# Display.net
KiCad netlist of a schematic drawn in Altium Designer
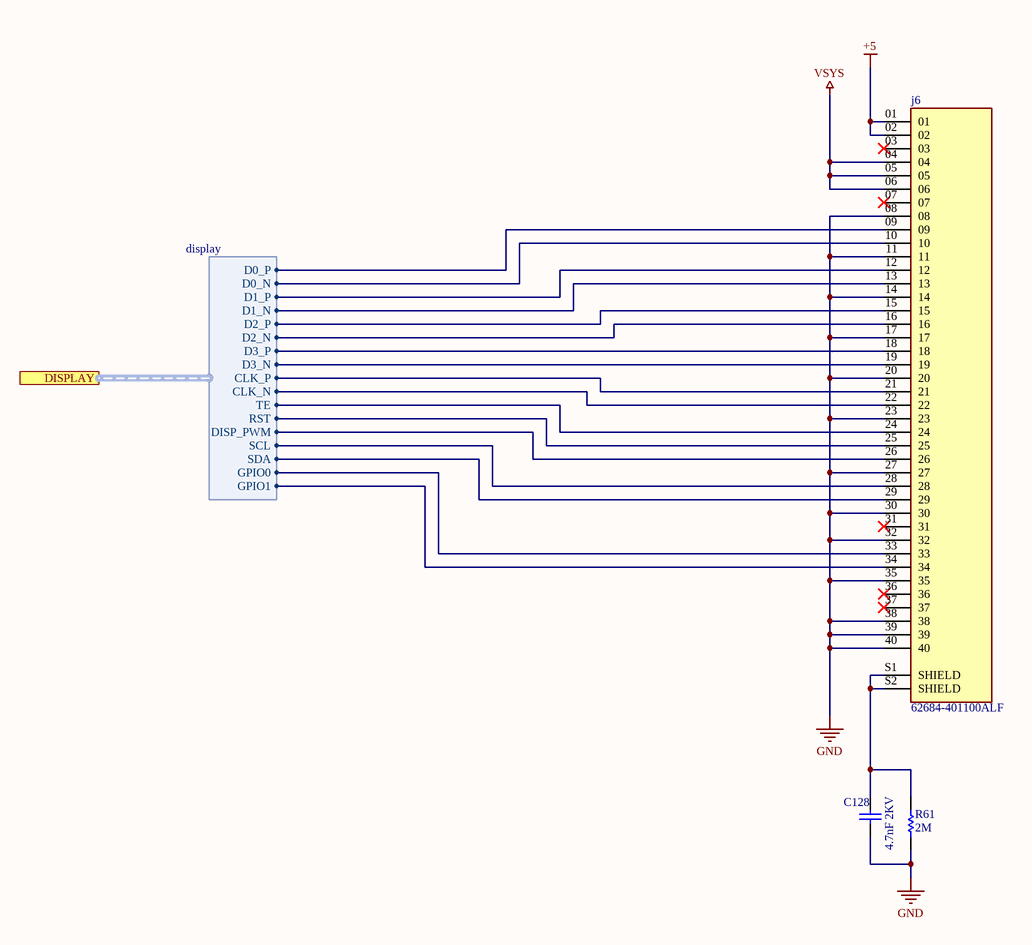
[diagram p0: Display.SchDoc]

(export (version "E")
  (design (tool "Eeschema 10.0.6"))
  (components
    (comp (ref "C128")
      (value "4.7nF 2KV")
      (footprint "C1210")
      (fields (field (name "Comment") "C1210"))
      (libsource (lib "kit") (part "C1210"))
    )
    (comp (ref "j6")
      (value "62684-401100ALF")
      (footprint "AMPHENOL_62684-401100ALF")
      (libsource (lib "kit") (part "62684-401100ALF"))
    )
    (comp (ref "R61")
      (value "2M")
      (footprint "R0603")
      (fields (field (name "Comment") "R0603"))
      (libsource (lib "kit") (part "R0603"))
    )
  )
  (nets
    (net (code "2") (name "+5") (class "Default")
      (node (ref "j6") (pin "01") (pinfunction "01_01") (pintype "passive"))
      (node (ref "j6") (pin "02") (pinfunction "02_02") (pintype "passive"))
    )
    (net (code "3") (name "/CLK_N") (class "Default")
      (node (ref "j6") (pin "22") (pinfunction "22_22") (pintype "passive"))
    )
    (net (code "4") (name "/CLK_P") (class "Default")
      (node (ref "j6") (pin "21") (pinfunction "21_21") (pintype "passive"))
    )
    (net (code "5") (name "/D0_N") (class "Default")
      (node (ref "j6") (pin "10") (pinfunction "10_10") (pintype "passive"))
    )
    (net (code "6") (name "/D0_P") (class "Default")
      (node (ref "j6") (pin "09") (pinfunction "09_09") (pintype "passive"))
    )
    (net (code "7") (name "/D1_N") (class "Default")
      (node (ref "j6") (pin "13") (pinfunction "13_13") (pintype "passive"))
    )
    (net (code "8") (name "/D1_P") (class "Default")
      (node (ref "j6") (pin "12") (pinfunction "12_12") (pintype "passive"))
    )
    (net (code "9") (name "/D2_N") (class "Default")
      (node (ref "j6") (pin "16") (pinfunction "16_16") (pintype "passive"))
    )
    (net (code "10") (name "/D2_P") (class "Default")
      (node (ref "j6") (pin "15") (pinfunction "15_15") (pintype "passive"))
    )
    (net (code "11") (name "/D3_N") (class "Default")
      (node (ref "j6") (pin "19") (pinfunction "19_19") (pintype "passive"))
    )
    (net (code "12") (name "/D3_P") (class "Default")
      (node (ref "j6") (pin "18") (pinfunction "18_18") (pintype "passive"))
    )
    (net (code "13") (name "/DISP_PWM") (class "Default")
      (node (ref "j6") (pin "26") (pinfunction "26_26") (pintype "passive"))
    )
    (net (code "14") (name "/GPIO0") (class "Default")
      (node (ref "j6") (pin "33") (pinfunction "33_33") (pintype "passive"))
    )
    (net (code "15") (name "/GPIO1") (class "Default")
      (node (ref "j6") (pin "34") (pinfunction "34_34") (pintype "passive"))
    )
    (net (code "16") (name "/RST") (class "Default")
      (node (ref "j6") (pin "25") (pinfunction "25_25") (pintype "passive"))
    )
    (net (code "17") (name "/SCL") (class "Default")
      (node (ref "j6") (pin "28") (pinfunction "28_28") (pintype "passive"))
    )
    (net (code "18") (name "/SDA") (class "Default")
      (node (ref "j6") (pin "29") (pinfunction "29_29") (pintype "passive"))
    )
    (net (code "19") (name "/TE") (class "Default")
      (node (ref "j6") (pin "24") (pinfunction "24_24") (pintype "passive"))
    )
    (net (code "21") (name "GND") (class "Default")
      (node (ref "C128") (pin "1") (pinfunction "1_1") (pintype "passive"))
      (node (ref "R61") (pin "2") (pinfunction "2_2") (pintype "passive"))
      (node (ref "j6") (pin "08") (pinfunction "08_08") (pintype "passive"))
      (node (ref "j6") (pin "11") (pinfunction "11_11") (pintype "passive"))
      (node (ref "j6") (pin "14") (pinfunction "14_14") (pintype "passive"))
      (node (ref "j6") (pin "17") (pinfunction "17_17") (pintype "passive"))
      (node (ref "j6") (pin "20") (pinfunction "20_20") (pintype "passive"))
      (node (ref "j6") (pin "23") (pinfunction "23_23") (pintype "passive"))
      (node (ref "j6") (pin "27") (pinfunction "27_27") (pintype "passive"))
      (node (ref "j6") (pin "30") (pinfunction "30_30") (pintype "passive"))
      (node (ref "j6") (pin "32") (pinfunction "32_32") (pintype "passive"))
      (node (ref "j6") (pin "35") (pinfunction "35_35") (pintype "passive"))
      (node (ref "j6") (pin "38") (pinfunction "38_38") (pintype "passive"))
      (node (ref "j6") (pin "39") (pinfunction "39_39") (pintype "passive"))
      (node (ref "j6") (pin "40") (pinfunction "40_40") (pintype "passive"))
    )
    (net (code "22") (name "Net-(C128-Pad2)") (class "Default")
      (node (ref "C128") (pin "2") (pinfunction "2_2") (pintype "passive"))
      (node (ref "R61") (pin "1") (pinfunction "1_1") (pintype "passive"))
      (node (ref "j6") (pin "S1") (pinfunction "SHIELD_S1") (pintype "passive"))
      (node (ref "j6") (pin "S2") (pinfunction "SHIELD_S2") (pintype "passive"))
    )
    (net (code "23") (name "VSYS") (class "Default")
      (node (ref "j6") (pin "04") (pinfunction "04_04") (pintype "passive"))
      (node (ref "j6") (pin "05") (pinfunction "05_05") (pintype "passive"))
      (node (ref "j6") (pin "06") (pinfunction "06_06") (pintype "passive"))
    )
    (net (code "24") (name "unconnected-(j6-Pad03)") (class "Default")
      (node (ref "j6") (pin "03") (pinfunction "03_03") (pintype "passive+no_connect"))
    )
    (net (code "25") (name "unconnected-(j6-Pad07)") (class "Default")
      (node (ref "j6") (pin "07") (pinfunction "07_07") (pintype "passive+no_connect"))
    )
    (net (code "26") (name "unconnected-(j6-Pad31)") (class "Default")
      (node (ref "j6") (pin "31") (pinfunction "31_31") (pintype "passive+no_connect"))
    )
    (net (code "27") (name "unconnected-(j6-Pad36)") (class "Default")
      (node (ref "j6") (pin "36") (pinfunction "36_36") (pintype "passive+no_connect"))
    )
    (net (code "28") (name "unconnected-(j6-Pad37)") (class "Default")
      (node (ref "j6") (pin "37") (pinfunction "37_37") (pintype "passive+no_connect"))
    )
  )
)
